# USB_Control_Unit_UCU.net
KiCad netlist of a schematic drawn in Altium Designer
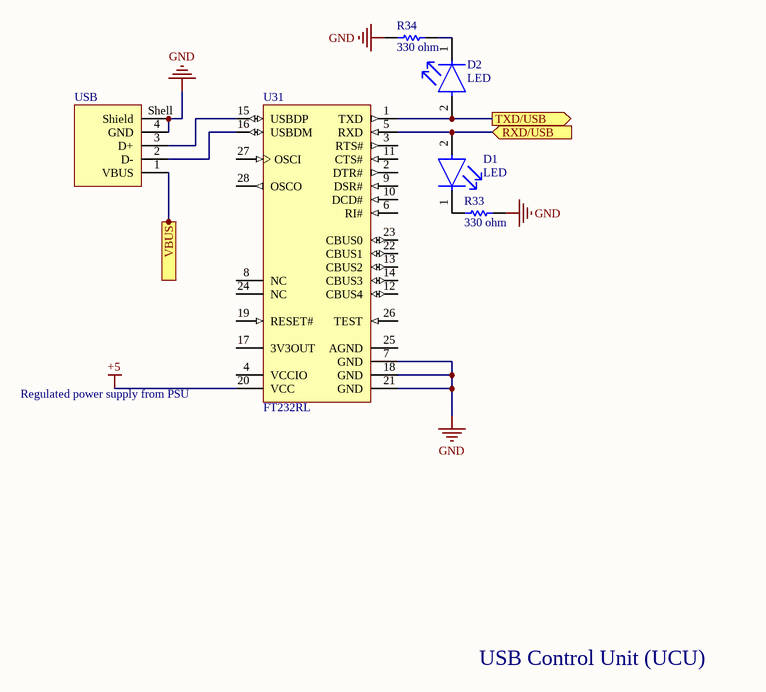
[diagram p0: USB Control Unit (UCU).SchDoc]

(export (version "E")
  (design (tool "Eeschema 10.0.6"))
  (components
    (comp (ref "D1")
      (value "LED")
      (footprint "FP-LTST-S270KRKT-MFG")
      (description "LED RED CLEAR CHIP SMD R/A")
      (libsource (lib "Altium Content Vault") (part "8706943c75ba83719d021d2fdc84c58"))
    )
    (comp (ref "D2")
      (value "LED")
      (footprint "FP-LTST-S270KRKT-MFG")
      (description "LED RED CLEAR CHIP SMD R/A")
      (libsource (lib "Altium Content Vault") (part "8706943c75ba83719d021d2fdc84c58"))
    )
    (comp (ref "R33")
      (value "330 ohm")
      (footprint "RESC1608X55X30LL15T15")
      (description "Chip Resistor, 330 Ohm, +/- 1%, 0.1 W, -55 to 155 degC, 0603 (1608 Metric), RoHS, Tape and Reel")
      (libsource (lib "Altium Content Vault") (part "RES-2"))
    )
    (comp (ref "R34")
      (value "330 ohm")
      (footprint "RESC1608X55X30LL15T15")
      (description "Chip Resistor, 330 Ohm, +/- 1%, 0.1 W, -55 to 155 degC, 0603 (1608 Metric), RoHS, Tape and Reel")
      (libsource (lib "Altium Content Vault") (part "RES-2"))
    )
    (comp (ref "U31")
      (value "FT232RL")
      (footprint "FTDI-SSOP-28_M")
      (description "IC USB FS SERIAL UART 28-SSOP")
      (fields (field (name "MANUFACTURER") "FTDI"))
      (libsource (lib "Altium Content Vault") (part "FTDI-FT232-SSOP-28"))
    )
    (comp (ref "USB")
      (value "61400416121")
      (footprint "61400416121")
      (libsource (lib "Altium Content Vault") (part "USB 2.0_Type B_Receptacle_1 Port"))
    )
  )
  (nets
    (net (code "1") (name "+5") (class "Default")
      (node (ref "U31") (pin "20") (pinfunction "VCC_20") (pintype "power_in"))
    )
    (net (code "2") (name "/RXD{slash}USB") (class "Default")
      (node (ref "D1") (pin "2") (pinfunction "A_2") (pintype "passive"))
      (node (ref "U31") (pin "5") (pinfunction "RXD_5") (pintype "input"))
    )
    (net (code "3") (name "/TXD{slash}USB") (class "Default")
      (node (ref "D2") (pin "2") (pinfunction "A_2") (pintype "passive"))
      (node (ref "U31") (pin "1") (pinfunction "TXD_1") (pintype "output"))
    )
    (net (code "4") (name "/VBUS") (class "Default")
      (node (ref "USB") (pin "1") (pinfunction "VBUS_1") (pintype "passive"))
    )
    (net (code "5") (name "GND") (class "Default")
      (node (ref "R33") (pin "1") (pinfunction "1_1") (pintype "passive"))
      (node (ref "R34") (pin "1") (pinfunction "1_1") (pintype "passive"))
      (node (ref "U31") (pin "18") (pinfunction "GND_18") (pintype "power_in"))
      (node (ref "U31") (pin "21") (pinfunction "GND_21") (pintype "power_in"))
      (node (ref "U31") (pin "7") (pinfunction "GND_7") (pintype "power_in"))
      (node (ref "USB") (pin "4") (pinfunction "GND_4") (pintype "passive"))
      (node (ref "USB") (pin "Shell") (pinfunction "Shield_Shell") (pintype "passive"))
    )
    (net (code "6") (name "Net-(D1-C)") (class "Default")
      (node (ref "D1") (pin "1") (pinfunction "C_1") (pintype "passive"))
      (node (ref "R33") (pin "2") (pinfunction "2_2") (pintype "passive"))
    )
    (net (code "7") (name "Net-(D2-C)") (class "Default")
      (node (ref "D2") (pin "1") (pinfunction "C_1") (pintype "passive"))
      (node (ref "R34") (pin "2") (pinfunction "2_2") (pintype "passive"))
    )
    (net (code "8") (name "Net-(U31-USBDM)") (class "Default")
      (node (ref "U31") (pin "16") (pinfunction "USBDM_16") (pintype "bidirectional"))
      (node (ref "USB") (pin "2") (pinfunction "D-_2") (pintype "passive"))
    )
    (net (code "9") (name "Net-(U31-USBDP)") (class "Default")
      (node (ref "U31") (pin "15") (pinfunction "USBDP_15") (pintype "bidirectional"))
      (node (ref "USB") (pin "3") (pinfunction "D+_3") (pintype "passive"))
    )
    (net (code "10") (name "unconnected-(U31-3V3OUT-Pad17)") (class "Default")
      (node (ref "U31") (pin "17") (pinfunction "3V3OUT_17") (pintype "power_in"))
    )
    (net (code "11") (name "unconnected-(U31-AGND-Pad25)") (class "Default")
      (node (ref "U31") (pin "25") (pinfunction "AGND_25") (pintype "power_in"))
    )
    (net (code "12") (name "unconnected-(U31-CBUS0-Pad23)") (class "Default")
      (node (ref "U31") (pin "23") (pinfunction "CBUS0_23") (pintype "bidirectional"))
    )
    (net (code "13") (name "unconnected-(U31-CBUS1-Pad22)") (class "Default")
      (node (ref "U31") (pin "22") (pinfunction "CBUS1_22") (pintype "bidirectional"))
    )
    (net (code "14") (name "unconnected-(U31-CBUS2-Pad13)") (class "Default")
      (node (ref "U31") (pin "13") (pinfunction "CBUS2_13") (pintype "bidirectional"))
    )
    (net (code "15") (name "unconnected-(U31-CBUS3-Pad14)") (class "Default")
      (node (ref "U31") (pin "14") (pinfunction "CBUS3_14") (pintype "bidirectional"))
    )
    (net (code "16") (name "unconnected-(U31-CBUS4-Pad12)") (class "Default")
      (node (ref "U31") (pin "12") (pinfunction "CBUS4_12") (pintype "bidirectional"))
    )
    (net (code "17") (name "unconnected-(U31-CTS#-Pad11)") (class "Default")
      (node (ref "U31") (pin "11") (pinfunction "CTS#_11") (pintype "input"))
    )
    (net (code "18") (name "unconnected-(U31-DCD#-Pad10)") (class "Default")
      (node (ref "U31") (pin "10") (pinfunction "DCD#_10") (pintype "input"))
    )
    (net (code "19") (name "unconnected-(U31-DSR#-Pad9)") (class "Default")
      (node (ref "U31") (pin "9") (pinfunction "DSR#_9") (pintype "input"))
    )
    (net (code "20") (name "unconnected-(U31-DTR#-Pad2)") (class "Default")
      (node (ref "U31") (pin "2") (pinfunction "DTR#_2") (pintype "output"))
    )
    (net (code "21") (name "unconnected-(U31-NC-Pad8)") (class "Default")
      (node (ref "U31") (pin "8") (pinfunction "NC_8") (pintype "passive"))
    )
    (net (code "22") (name "unconnected-(U31-NC-Pad24)") (class "Default")
      (node (ref "U31") (pin "24") (pinfunction "NC_24") (pintype "passive"))
    )
    (net (code "23") (name "unconnected-(U31-OSCI-Pad27)") (class "Default")
      (node (ref "U31") (pin "27") (pinfunction "OSCI_27") (pintype "input"))
    )
    (net (code "24") (name "unconnected-(U31-OSCO-Pad28)") (class "Default")
      (node (ref "U31") (pin "28") (pinfunction "OSCO_28") (pintype "output"))
    )
    (net (code "25") (name "unconnected-(U31-RESET#-Pad19)") (class "Default")
      (node (ref "U31") (pin "19") (pinfunction "RESET#_19") (pintype "input"))
    )
    (net (code "26") (name "unconnected-(U31-RI#-Pad6)") (class "Default")
      (node (ref "U31") (pin "6") (pinfunction "RI#_6") (pintype "input"))
    )
    (net (code "27") (name "unconnected-(U31-RTS#-Pad3)") (class "Default")
      (node (ref "U31") (pin "3") (pinfunction "RTS#_3") (pintype "output"))
    )
    (net (code "28") (name "unconnected-(U31-TEST-Pad26)") (class "Default")
      (node (ref "U31") (pin "26") (pinfunction "TEST_26") (pintype "input"))
    )
    (net (code "29") (name "unconnected-(U31-VCCIO-Pad4)") (class "Default")
      (node (ref "U31") (pin "4") (pinfunction "VCCIO_4") (pintype "power_in"))
    )
  )
)
